# Power_3_3V_to_mc.net
KiCad netlist of a schematic drawn in Altium Designer
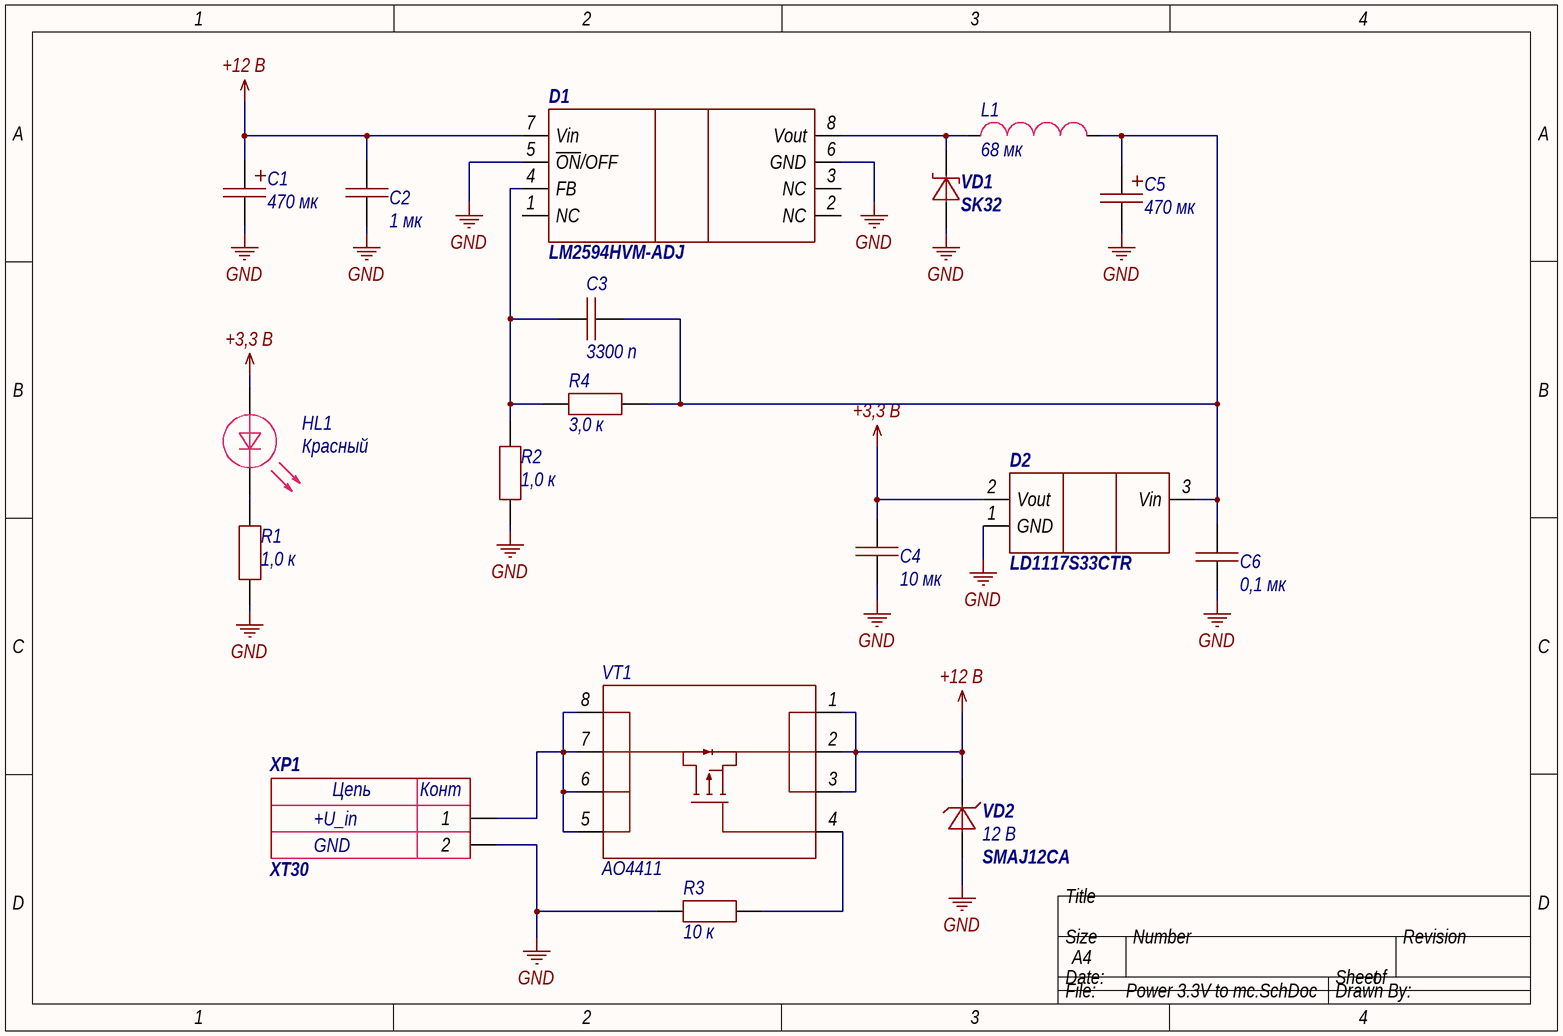
[diagram p0: Power 3.3V to mc.SchDoc]

(export (version "E")
  (design (tool "Eeschema 10.0.6"))
  (components
    (comp (ref "C1")
      (value "470 мк")
      (footprint "RADIAL-2_10mm")
      (description "Конденсатор электролит. 470 мкФ, 25 В, 10 мм")
      (fields (field (name "PART NUMBER") "Capacitor_polar"))
      (libsource (lib "Hydrolib") (part "Capacitor_polar"))
    )
    (comp (ref "C2")
      (value "1 мк")
      (footprint "0603C")
      (description "Конденсатор")
      (fields (field (name "PART NUMBER") "Capacitor_1u_10_50V_X7R_0603C") (field (name "TOLERANCE") "0,1"))
      (libsource (lib "Hydrolib") (part "Capacitor"))
    )
    (comp (ref "C3")
      (value "3300 п")
      (footprint "0603C")
      (description "Конденсатор")
      (fields (field (name "PART NUMBER") "Capacitor_3,3n_10_50V_X7R_0603C") (field (name "TOLERANCE") "0,1"))
      (libsource (lib "Hydrolib") (part "Capacitor"))
    )
    (comp (ref "C4")
      (value "10 мк")
      (footprint "1210C")
      (description "Конденсатор")
      (fields (field (name "PART NUMBER") "Capacitor_10u_10_35V_X7R_1210C") (field (name "TOLERANCE") "0,1"))
      (libsource (lib "Hydrolib") (part "Capacitor"))
    )
    (comp (ref "C5")
      (value "470 мк")
      (footprint "RADIAL-2_10mm")
      (description "Конденсатор электролит. 470 мкФ, 25 В, 10 мм")
      (fields (field (name "PART NUMBER") "Capacitor_polar"))
      (libsource (lib "Hydrolib") (part "Capacitor_polar"))
    )
    (comp (ref "C6")
      (value "0,1 мк")
      (footprint "0603C")
      (description "Конденсатор")
      (fields (field (name "PART NUMBER") "Capacitor_0,1u_10_50V_X7R_0603C") (field (name "TOLERANCE") "0,1"))
      (libsource (lib "Hydrolib") (part "Capacitor"))
    )
    (comp (ref "D1")
      (value "LM2594HVM-ADJ")
      (footprint "SOIC-8")
      (description "DC-DC преобразователь")
      (libsource (lib "Hydrolib") (part "LM2594HVM-ADJ"))
    )
    (comp (ref "D2")
      (value "LD1117S33CTR")
      (footprint "SOT223")
      (description "Линейный стабилизатор напряжения")
      (libsource (lib "Hydrolib") (part "LD1117S33CTR"))
    )
    (comp (ref "HL1")
      (value "LED")
      (footprint "0805D")
      (description "Светодиод")
      (fields (field (name "COLOR") "Красный"))
      (libsource (lib "Hydrolib") (part "LED"))
    )
    (comp (ref "L1")
      (value "68 мк")
      (footprint "7.3x7.3")
      (description "B82472G6683M, ЧИП-индуктивность экранированная 68мкГн ±20%, 0.82A, 26мОм")
      (fields (field (name "PART NUMBER") "B82472G6683M"))
      (libsource (lib "Hydrolib") (part "Inductance"))
    )
    (comp (ref "R1")
      (value "1,0 к")
      (footprint "0603R")
      (description "Резистор номиналом 1,0 кОм и точностью 1%")
      (fields (field (name "PART NUMBER") "Resistor_1.0k_1_0603") (field (name "TOLERANCE") "1%"))
      (libsource (lib "Hydrolib") (part "Resistor"))
    )
    (comp (ref "R2")
      (value "1,0 к")
      (footprint "0603R")
      (description "Резистор номиналом 1,0 кОм и точностью 1%")
      (fields (field (name "PART NUMBER") "Resistor_1.0k_1_0603") (field (name "TOLERANCE") "1%"))
      (libsource (lib "") (part "Resistor_2"))
    )
    (comp (ref "R3")
      (value "10 к")
      (footprint "0603R")
      (description "Резистор номиналом 10 кОм и точностью 1%")
      (fields (field (name "PART NUMBER") "Resistor_10k_1_0603") (field (name "TOLERANCE") "1%"))
      (libsource (lib "") (part "Resistor_1"))
    )
    (comp (ref "R4")
      (value "3,0 к")
      (footprint "0603R")
      (description "Резистор номиналом 3,0 кОм и точностью 1%")
      (fields (field (name "PART NUMBER") "Resistor_3.0k_1_0603") (field (name "TOLERANCE") "1%"))
      (libsource (lib "") (part "Resistor_1"))
    )
    (comp (ref "VD1")
      (value "SK32")
      (footprint "SMC")
      (description "Диод шоттки на 20 В, номинальный ток 3 А")
      (libsource (lib "Hydrolib") (part "Schottky_diode"))
    )
    (comp (ref "VD2")
      (value "SMAJ12CA")
      (footprint "SMA")
      (description "Защитный диод на 12 В, рассеиваемая мощность 400 Вт")
      (fields (field (name "ALTIUM_VALUE") "12 В"))
      (libsource (lib "Hydrolib") (part "TVS_1_1dir"))
    )
    (comp (ref "VT1")
      (value "AO4411")
      (footprint "SOIC-8")
      (description "P-канальный MOSFET")
      (libsource (lib "Hydrolib") (part "MOSFET_P-channel_8pin"))
    )
    (comp (ref "XP1")
      (value "XT30")
      (footprint "XT30")
      (description "2-пиновый разъем с ключом")
      (fields (field (name "VALUE2") "GND") (field (name "VALUE1") "+U_in"))
      (libsource (lib "Hydrolib") (part "Conn_2pin"))
    )
  )
  (nets
    (net (code "1") (name "+3,3 В") (class "Default")
      (node (ref "C4") (pin "1") (pinfunction "1_1") (pintype "passive"))
      (node (ref "D2") (pin "2") (pinfunction "Vout_2") (pintype "passive"))
      (node (ref "HL1") (pin "1") (pinfunction "1_1") (pintype "passive"))
    )
    (net (code "2") (name "+12 В") (class "Default")
      (node (ref "C1") (pin "1") (pinfunction "1_1") (pintype "passive"))
      (node (ref "C2") (pin "1") (pinfunction "1_1") (pintype "passive"))
      (node (ref "D1") (pin "7") (pinfunction "Vin_7") (pintype "passive"))
      (node (ref "VD2") (pin "2") (pinfunction "2_2") (pintype "passive"))
      (node (ref "VT1") (pin "1") (pinfunction "1_1") (pintype "passive"))
      (node (ref "VT1") (pin "2") (pinfunction "2_2") (pintype "passive"))
      (node (ref "VT1") (pin "3") (pinfunction "3_3") (pintype "passive"))
    )
    (net (code "3") (name "GND") (class "Default")
      (node (ref "C1") (pin "2") (pinfunction "2_2") (pintype "passive"))
      (node (ref "C2") (pin "2") (pinfunction "2_2") (pintype "passive"))
      (node (ref "C4") (pin "2") (pinfunction "2_2") (pintype "passive"))
      (node (ref "C5") (pin "2") (pinfunction "2_2") (pintype "passive"))
      (node (ref "C6") (pin "2") (pinfunction "2_2") (pintype "passive"))
      (node (ref "D1") (pin "5") (pinfunction "~{ON}/OFF_5") (pintype "passive"))
      (node (ref "D1") (pin "6") (pinfunction "GND_6") (pintype "passive"))
      (node (ref "D2") (pin "1") (pinfunction "GND_1") (pintype "passive"))
      (node (ref "R1") (pin "2") (pinfunction "2_2") (pintype "passive"))
      (node (ref "R2") (pin "1") (pinfunction "1_1") (pintype "passive"))
      (node (ref "R3") (pin "1") (pinfunction "1_1") (pintype "passive"))
      (node (ref "VD1") (pin "1") (pinfunction "1_1") (pintype "passive"))
      (node (ref "VD2") (pin "1") (pinfunction "1_1") (pintype "passive"))
      (node (ref "XP1") (pin "2") (pinfunction "2_2") (pintype "passive"))
    )
    (net (code "4") (name "Net-(D1-FB)") (class "Default")
      (node (ref "C3") (pin "1") (pinfunction "1_1") (pintype "passive"))
      (node (ref "D1") (pin "4") (pinfunction "FB_4") (pintype "passive"))
      (node (ref "R2") (pin "2") (pinfunction "2_2") (pintype "passive"))
      (node (ref "R4") (pin "1") (pinfunction "1_1") (pintype "passive"))
    )
    (net (code "5") (name "Net-(D1-Vout)") (class "Default")
      (node (ref "D1") (pin "8") (pinfunction "Vout_8") (pintype "passive"))
      (node (ref "L1") (pin "1") (pinfunction "1_1") (pintype "passive"))
      (node (ref "VD1") (pin "2") (pinfunction "2_2") (pintype "passive"))
    )
    (net (code "6") (name "Net-(D2-Vin)") (class "Default")
      (node (ref "C3") (pin "2") (pinfunction "2_2") (pintype "passive"))
      (node (ref "C5") (pin "1") (pinfunction "1_1") (pintype "passive"))
      (node (ref "C6") (pin "1") (pinfunction "1_1") (pintype "passive"))
      (node (ref "D2") (pin "3") (pinfunction "Vin_3") (pintype "passive"))
      (node (ref "L1") (pin "2") (pinfunction "2_2") (pintype "passive"))
      (node (ref "R4") (pin "2") (pinfunction "2_2") (pintype "passive"))
    )
    (net (code "7") (name "Net-(HL1-Pad2)") (class "Default")
      (node (ref "HL1") (pin "2") (pinfunction "2_2") (pintype "passive"))
      (node (ref "R1") (pin "1") (pinfunction "1_1") (pintype "passive"))
    )
    (net (code "8") (name "Net-(R3-Pad2)") (class "Default")
      (node (ref "R3") (pin "2") (pinfunction "2_2") (pintype "passive"))
      (node (ref "VT1") (pin "4") (pinfunction "4_4") (pintype "passive"))
    )
    (net (code "9") (name "Net-(VT1-Pad5)") (class "Default")
      (node (ref "VT1") (pin "5") (pinfunction "5_5") (pintype "passive"))
      (node (ref "VT1") (pin "6") (pinfunction "6_6") (pintype "passive"))
      (node (ref "VT1") (pin "7") (pinfunction "7_7") (pintype "passive"))
      (node (ref "VT1") (pin "8") (pinfunction "8_8") (pintype "passive"))
      (node (ref "XP1") (pin "1") (pinfunction "1_1") (pintype "passive"))
    )
    (net (code "10") (name "unconnected-(D1-NC-Pad1)") (class "Default")
      (node (ref "D1") (pin "1") (pinfunction "NC_1") (pintype "passive"))
    )
    (net (code "11") (name "unconnected-(D1-NC-Pad2)") (class "Default")
      (node (ref "D1") (pin "2") (pinfunction "NC_2") (pintype "passive"))
    )
    (net (code "12") (name "unconnected-(D1-NC-Pad3)") (class "Default")
      (node (ref "D1") (pin "3") (pinfunction "NC_3") (pintype "passive"))
    )
  )
)
